# Sheet4.net
KiCad netlist of a schematic drawn in Altium Designer
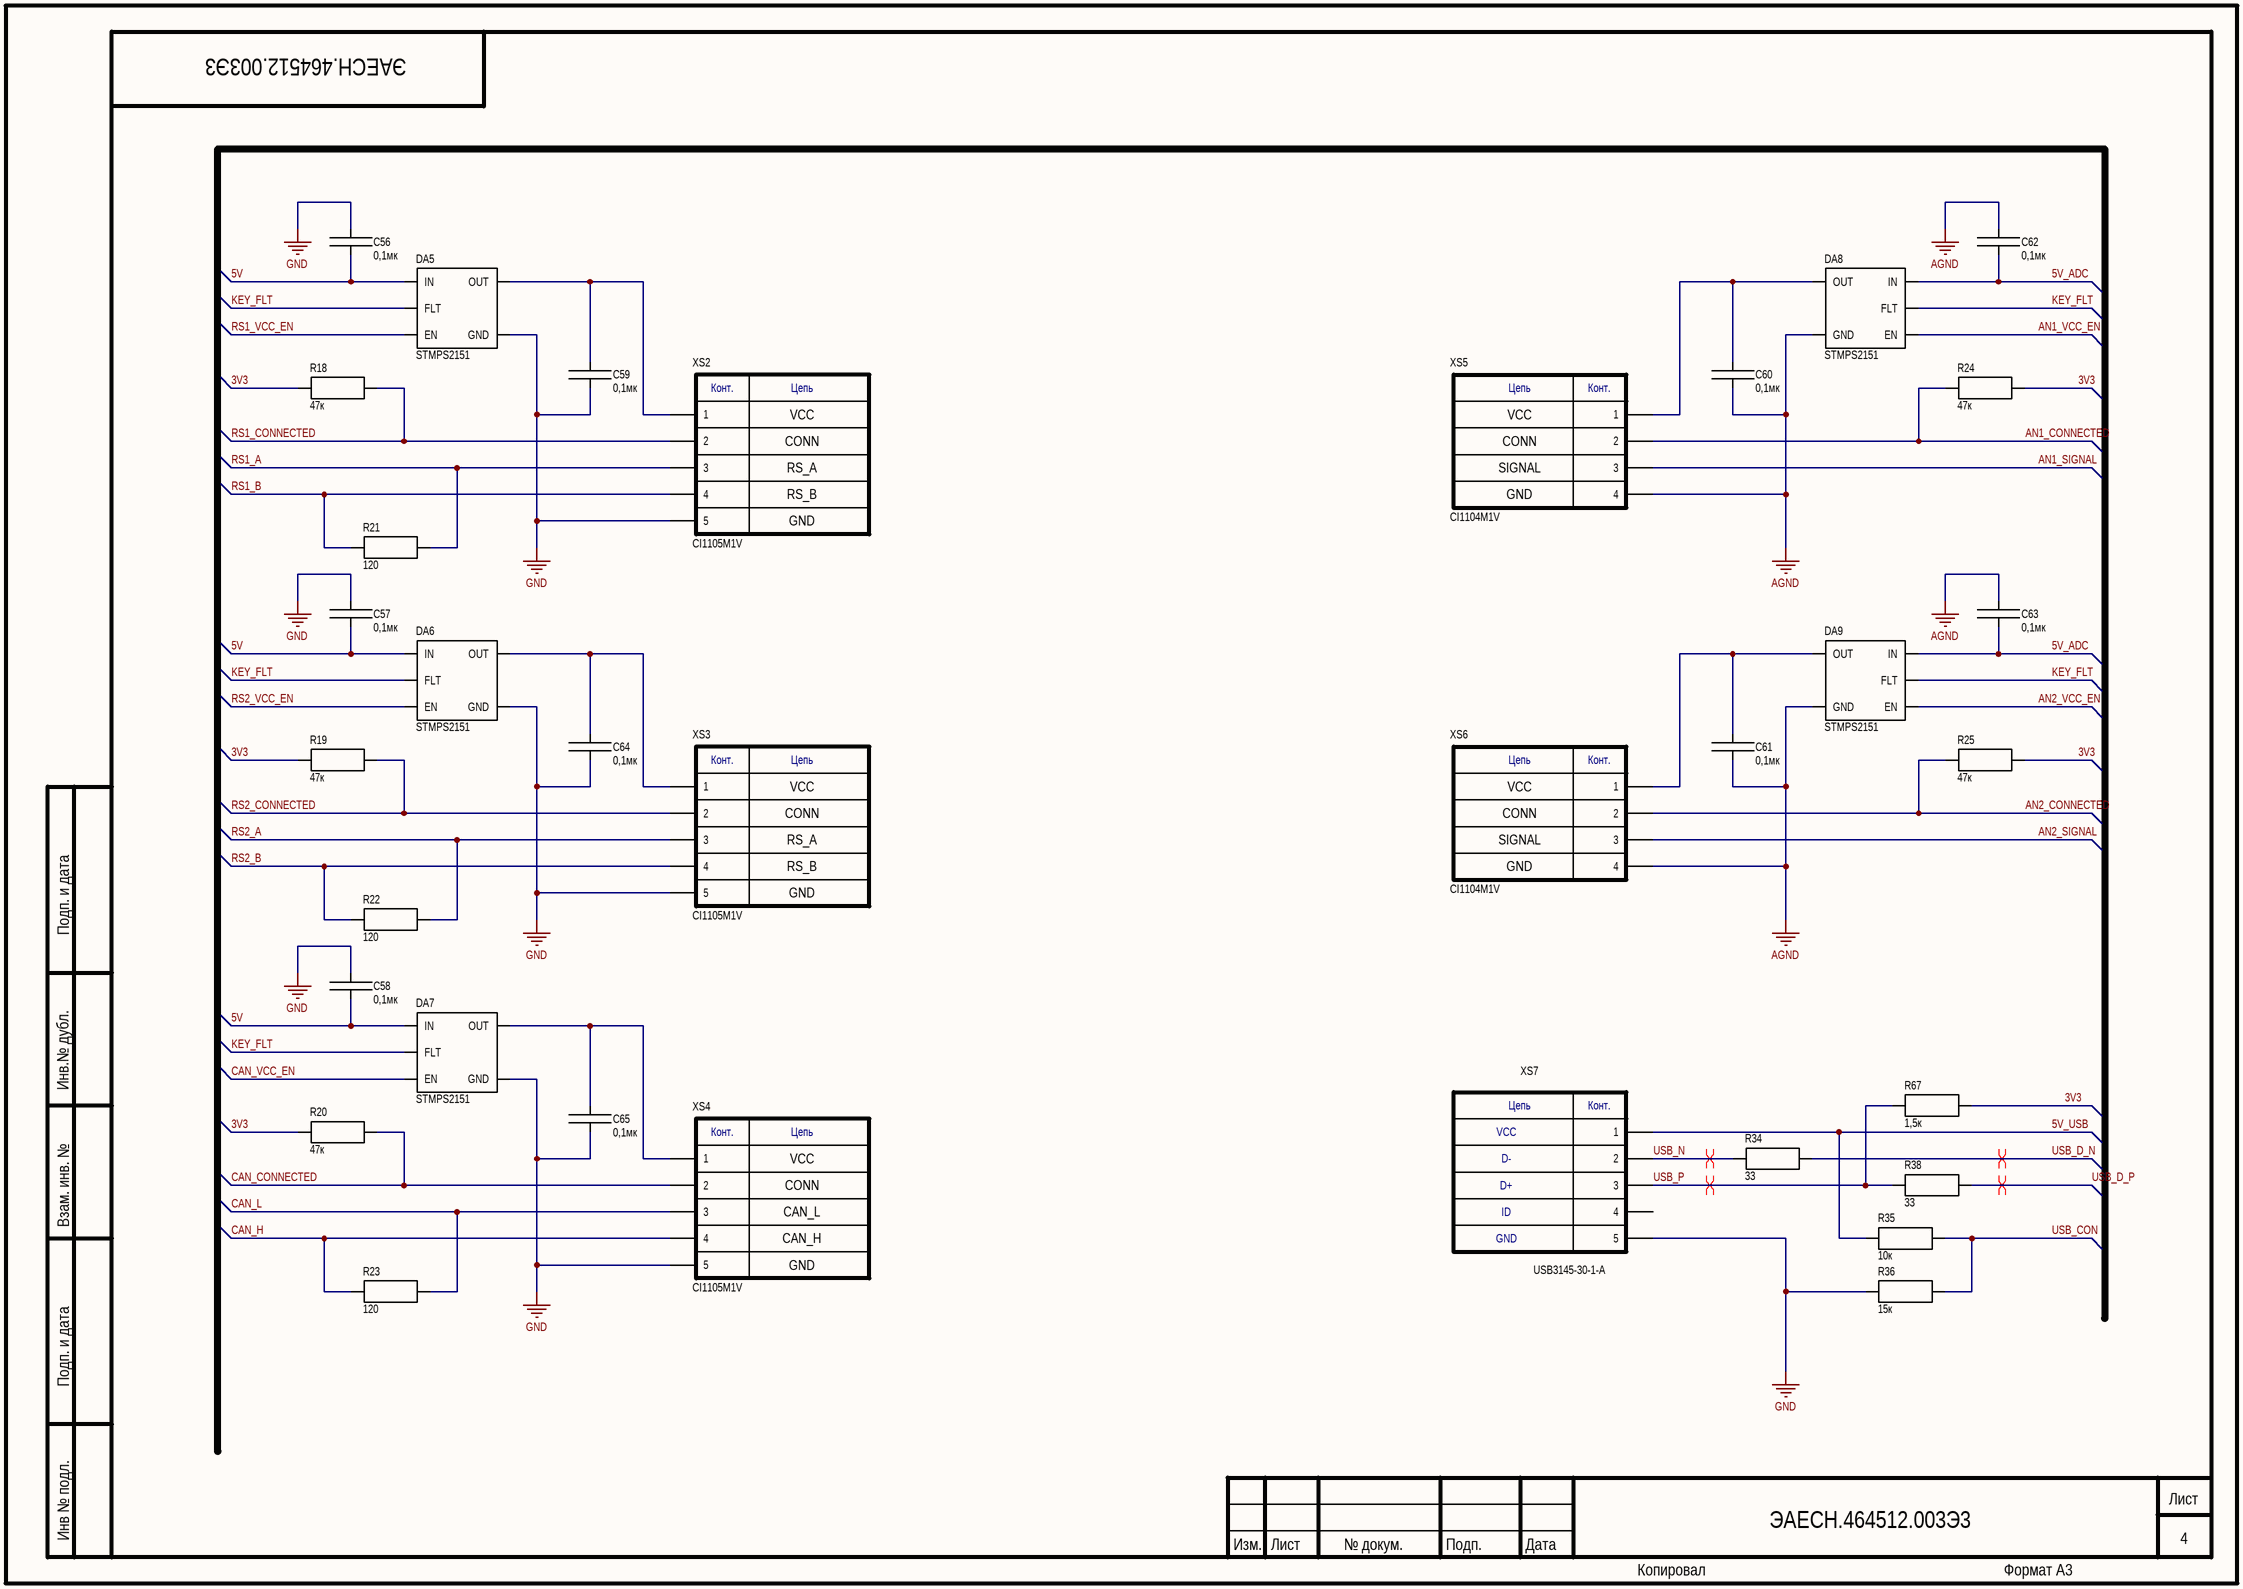
[diagram p0: Sheet4.SchDoc]

(export (version "E")
  (design (tool "Eeschema 10.0.6"))
  (components
    (comp (ref "C56")
      (value "0,1мк")
      (footprint "С0603")
      (fields (field (name "Comment") "C"))
      (libsource (lib "Schlib1") (part "C"))
    )
    (comp (ref "C57")
      (value "0,1мк")
      (footprint "С0603")
      (fields (field (name "Comment") "C"))
      (libsource (lib "Schlib1") (part "C"))
    )
    (comp (ref "C58")
      (value "0,1мк")
      (footprint "С0603")
      (fields (field (name "Comment") "C"))
      (libsource (lib "Schlib1") (part "C"))
    )
    (comp (ref "C59")
      (value "0,1мк")
      (footprint "С0603")
      (fields (field (name "Comment") "C"))
      (libsource (lib "Schlib1") (part "C"))
    )
    (comp (ref "C60")
      (value "0,1мк")
      (footprint "С0603")
      (fields (field (name "Comment") "C"))
      (libsource (lib "Schlib1") (part "C"))
    )
    (comp (ref "C61")
      (value "0,1мк")
      (footprint "С0603")
      (fields (field (name "Comment") "C"))
      (libsource (lib "Schlib1") (part "C"))
    )
    (comp (ref "C62")
      (value "0,1мк")
      (footprint "С0603")
      (fields (field (name "Comment") "C"))
      (libsource (lib "Schlib1") (part "C"))
    )
    (comp (ref "C63")
      (value "0,1мк")
      (footprint "С0603")
      (fields (field (name "Comment") "C"))
      (libsource (lib "Schlib1") (part "C"))
    )
    (comp (ref "C64")
      (value "0,1мк")
      (footprint "С0603")
      (fields (field (name "Comment") "C"))
      (libsource (lib "Schlib1") (part "C"))
    )
    (comp (ref "C65")
      (value "0,1мк")
      (footprint "С0603")
      (fields (field (name "Comment") "C"))
      (libsource (lib "Schlib1") (part "C"))
    )
    (comp (ref "DA5")
      (value "STMPS2151")
      (footprint "SOT-23-5")
      (libsource (lib "Schlib1") (part "STMPS21x1"))
    )
    (comp (ref "DA6")
      (value "STMPS2151")
      (footprint "SOT-23-5")
      (libsource (lib "Schlib1") (part "STMPS21x1"))
    )
    (comp (ref "DA7")
      (value "STMPS2151")
      (footprint "SOT-23-5")
      (libsource (lib "Schlib1") (part "STMPS21x1"))
    )
    (comp (ref "DA8")
      (value "STMPS2151")
      (footprint "SOT-23-5")
      (libsource (lib "Schlib1") (part "STMPS21x1"))
    )
    (comp (ref "DA9")
      (value "STMPS2151")
      (footprint "SOT-23-5")
      (libsource (lib "Schlib1") (part "STMPS21x1"))
    )
    (comp (ref "R18")
      (value "47к")
      (footprint "R0603")
      (fields (field (name "Comment") "R"))
      (libsource (lib "Schlib1") (part "R"))
    )
    (comp (ref "R19")
      (value "47к")
      (footprint "R0603")
      (fields (field (name "Comment") "R"))
      (libsource (lib "Schlib1") (part "R"))
    )
    (comp (ref "R20")
      (value "47к")
      (footprint "R0603")
      (fields (field (name "Comment") "R"))
      (libsource (lib "Schlib1") (part "R"))
    )
    (comp (ref "R21")
      (value "120")
      (footprint "R1206")
      (fields (field (name "Comment") "R"))
      (libsource (lib "Schlib1") (part "R"))
    )
    (comp (ref "R22")
      (value "120")
      (footprint "R1206")
      (fields (field (name "Comment") "R"))
      (libsource (lib "Schlib1") (part "R"))
    )
    (comp (ref "R23")
      (value "120")
      (footprint "R1206")
      (fields (field (name "Comment") "R"))
      (libsource (lib "Schlib1") (part "R"))
    )
    (comp (ref "R24")
      (value "47к")
      (footprint "R0603")
      (fields (field (name "Comment") "R"))
      (libsource (lib "Schlib1") (part "R"))
    )
    (comp (ref "R25")
      (value "47к")
      (footprint "R0603")
      (fields (field (name "Comment") "R"))
      (libsource (lib "Schlib1") (part "R"))
    )
    (comp (ref "R34")
      (value "33")
      (footprint "R0603")
      (fields (field (name "Comment") "R"))
      (libsource (lib "Schlib1") (part "R"))
    )
    (comp (ref "R35")
      (value "10к")
      (footprint "R0603")
      (fields (field (name "Comment") "R"))
      (libsource (lib "Schlib1") (part "R"))
    )
    (comp (ref "R36")
      (value "15к")
      (footprint "R0603")
      (fields (field (name "Comment") "R"))
      (libsource (lib "Schlib1") (part "R"))
    )
    (comp (ref "R38")
      (value "33")
      (footprint "R0603")
      (fields (field (name "Comment") "R"))
      (libsource (lib "Schlib1") (part "R"))
    )
    (comp (ref "R67")
      (value "1,5к")
      (footprint "R0603")
      (fields (field (name "Comment") "R"))
      (libsource (lib "Schlib1") (part "R"))
    )
    (comp (ref "XS2") (value "CI1105M1V") (footprint "СI1105М1V") (libsource (lib "Schlib1") (part "5pin")))
    (comp (ref "XS3") (value "CI1105M1V") (footprint "СI1105М1V") (libsource (lib "Schlib1") (part "5pin")))
    (comp (ref "XS4") (value "CI1105M1V") (footprint "СI1105М1V") (libsource (lib "Schlib1") (part "5pin")))
    (comp (ref "XS5") (value "СI1104М1V") (footprint "СI1104М1V") (libsource (lib "Schlib1") (part "4pin")))
    (comp (ref "XS6") (value "СI1104М1V") (footprint "СI1104М1V") (libsource (lib "Schlib1") (part "4pin")))
    (comp (ref "XS7")
      (value "USB3145-30-1-A")
      (footprint "USB3145-30-1")
      (libsource (lib "Schlib1") (part "USB"))
    )
  )
  (nets
    (net (code "1") (name "/3V3") (class "Default")
      (node (ref "R18") (pin "1") (pinfunction "1_1") (pintype "passive"))
      (node (ref "R19") (pin "1") (pinfunction "1_1") (pintype "passive"))
      (node (ref "R20") (pin "1") (pinfunction "1_1") (pintype "passive"))
      (node (ref "R24") (pin "1") (pinfunction "1_1") (pintype "passive"))
      (node (ref "R25") (pin "1") (pinfunction "1_1") (pintype "passive"))
      (node (ref "R67") (pin "2") (pinfunction "2_2") (pintype "passive"))
    )
    (net (code "2") (name "/5V") (class "Default")
      (node (ref "C56") (pin "2") (pinfunction "2_2") (pintype "passive"))
      (node (ref "C57") (pin "2") (pinfunction "2_2") (pintype "passive"))
      (node (ref "C58") (pin "2") (pinfunction "2_2") (pintype "passive"))
      (node (ref "DA5") (pin "5") (pinfunction "IN_5") (pintype "passive"))
      (node (ref "DA6") (pin "5") (pinfunction "IN_5") (pintype "passive"))
      (node (ref "DA7") (pin "5") (pinfunction "IN_5") (pintype "passive"))
    )
    (net (code "3") (name "/5V_ADC") (class "Default")
      (node (ref "C62") (pin "2") (pinfunction "2_2") (pintype "passive"))
      (node (ref "C63") (pin "2") (pinfunction "2_2") (pintype "passive"))
      (node (ref "DA8") (pin "5") (pinfunction "IN_5") (pintype "passive"))
      (node (ref "DA9") (pin "5") (pinfunction "IN_5") (pintype "passive"))
    )
    (net (code "4") (name "/5V_USB") (class "Default")
      (node (ref "R35") (pin "1") (pinfunction "1_1") (pintype "passive"))
      (node (ref "XS7") (pin "1") (pinfunction "1_1") (pintype "passive"))
    )
    (net (code "5") (name "/AN1_CONNECTED") (class "Default")
      (node (ref "R24") (pin "2") (pinfunction "2_2") (pintype "passive"))
      (node (ref "XS5") (pin "2") (pinfunction "2_2") (pintype "passive"))
    )
    (net (code "6") (name "/AN1_SIGNAL") (class "Default")
      (node (ref "XS5") (pin "3") (pinfunction "3_3") (pintype "passive"))
    )
    (net (code "7") (name "/AN1_VCC_EN") (class "Default")
      (node (ref "DA8") (pin "4") (pinfunction "EN_4") (pintype "passive"))
    )
    (net (code "8") (name "/AN2_CONNECTED") (class "Default")
      (node (ref "R25") (pin "2") (pinfunction "2_2") (pintype "passive"))
      (node (ref "XS6") (pin "2") (pinfunction "2_2") (pintype "passive"))
    )
    (net (code "9") (name "/AN2_SIGNAL") (class "Default")
      (node (ref "XS6") (pin "3") (pinfunction "3_3") (pintype "passive"))
    )
    (net (code "10") (name "/AN2_VCC_EN") (class "Default")
      (node (ref "DA9") (pin "4") (pinfunction "EN_4") (pintype "passive"))
    )
    (net (code "11") (name "/CAN_CONNECTED") (class "Default")
      (node (ref "R20") (pin "2") (pinfunction "2_2") (pintype "passive"))
      (node (ref "XS4") (pin "2") (pinfunction "2_2") (pintype "passive"))
    )
    (net (code "12") (name "/CAN_H") (class "Default")
      (node (ref "R23") (pin "1") (pinfunction "1_1") (pintype "passive"))
      (node (ref "XS4") (pin "4") (pinfunction "4_4") (pintype "passive"))
    )
    (net (code "13") (name "/CAN_L") (class "Default")
      (node (ref "R23") (pin "2") (pinfunction "2_2") (pintype "passive"))
      (node (ref "XS4") (pin "3") (pinfunction "3_3") (pintype "passive"))
    )
    (net (code "14") (name "/CAN_VCC_EN") (class "Default")
      (node (ref "DA7") (pin "4") (pinfunction "EN_4") (pintype "passive"))
    )
    (net (code "15") (name "/KEY_FLT") (class "Default")
      (node (ref "DA5") (pin "3") (pinfunction "FLT_3") (pintype "passive"))
      (node (ref "DA6") (pin "3") (pinfunction "FLT_3") (pintype "passive"))
      (node (ref "DA7") (pin "3") (pinfunction "FLT_3") (pintype "passive"))
      (node (ref "DA8") (pin "3") (pinfunction "FLT_3") (pintype "passive"))
      (node (ref "DA9") (pin "3") (pinfunction "FLT_3") (pintype "passive"))
    )
    (net (code "16") (name "/RS1_A") (class "Default")
      (node (ref "R21") (pin "2") (pinfunction "2_2") (pintype "passive"))
      (node (ref "XS2") (pin "3") (pinfunction "3_3") (pintype "passive"))
    )
    (net (code "17") (name "/RS1_B") (class "Default")
      (node (ref "R21") (pin "1") (pinfunction "1_1") (pintype "passive"))
      (node (ref "XS2") (pin "4") (pinfunction "4_4") (pintype "passive"))
    )
    (net (code "18") (name "/RS1_CONNECTED") (class "Default")
      (node (ref "R18") (pin "2") (pinfunction "2_2") (pintype "passive"))
      (node (ref "XS2") (pin "2") (pinfunction "2_2") (pintype "passive"))
    )
    (net (code "19") (name "/RS1_VCC_EN") (class "Default")
      (node (ref "DA5") (pin "4") (pinfunction "EN_4") (pintype "passive"))
    )
    (net (code "20") (name "/RS2_A") (class "Default")
      (node (ref "R22") (pin "2") (pinfunction "2_2") (pintype "passive"))
      (node (ref "XS3") (pin "3") (pinfunction "3_3") (pintype "passive"))
    )
    (net (code "21") (name "/RS2_B") (class "Default")
      (node (ref "R22") (pin "1") (pinfunction "1_1") (pintype "passive"))
      (node (ref "XS3") (pin "4") (pinfunction "4_4") (pintype "passive"))
    )
    (net (code "22") (name "/RS2_CONNECTED") (class "Default")
      (node (ref "R19") (pin "2") (pinfunction "2_2") (pintype "passive"))
      (node (ref "XS3") (pin "2") (pinfunction "2_2") (pintype "passive"))
    )
    (net (code "23") (name "/RS2_VCC_EN") (class "Default")
      (node (ref "DA6") (pin "4") (pinfunction "EN_4") (pintype "passive"))
    )
    (net (code "24") (name "/USB_CON") (class "Default")
      (node (ref "R35") (pin "2") (pinfunction "2_2") (pintype "passive"))
      (node (ref "R36") (pin "2") (pinfunction "2_2") (pintype "passive"))
    )
    (net (code "25") (name "/USB_D_N") (class "Default")
      (node (ref "R34") (pin "2") (pinfunction "2_2") (pintype "passive"))
    )
    (net (code "26") (name "/USB_D_P") (class "Default")
      (node (ref "R38") (pin "2") (pinfunction "2_2") (pintype "passive"))
    )
    (net (code "27") (name "/USB_N") (class "Default")
      (node (ref "R34") (pin "1") (pinfunction "1_1") (pintype "passive"))
      (node (ref "XS7") (pin "2") (pinfunction "2_2") (pintype "passive"))
    )
    (net (code "28") (name "/USB_P") (class "Default")
      (node (ref "R38") (pin "1") (pinfunction "1_1") (pintype "passive"))
      (node (ref "R67") (pin "1") (pinfunction "1_1") (pintype "passive"))
      (node (ref "XS7") (pin "3") (pinfunction "3_3") (pintype "passive"))
    )
    (net (code "29") (name "AGND") (class "Default")
      (node (ref "C60") (pin "2") (pinfunction "2_2") (pintype "passive"))
      (node (ref "C61") (pin "2") (pinfunction "2_2") (pintype "passive"))
      (node (ref "C62") (pin "1") (pinfunction "1_1") (pintype "passive"))
      (node (ref "C63") (pin "1") (pinfunction "1_1") (pintype "passive"))
      (node (ref "DA8") (pin "2") (pinfunction "GND_2") (pintype "passive"))
      (node (ref "DA9") (pin "2") (pinfunction "GND_2") (pintype "passive"))
      (node (ref "XS5") (pin "4") (pinfunction "4_4") (pintype "passive"))
      (node (ref "XS6") (pin "4") (pinfunction "4_4") (pintype "passive"))
    )
    (net (code "30") (name "GND") (class "Default")
      (node (ref "C56") (pin "1") (pinfunction "1_1") (pintype "passive"))
      (node (ref "C57") (pin "1") (pinfunction "1_1") (pintype "passive"))
      (node (ref "C58") (pin "1") (pinfunction "1_1") (pintype "passive"))
      (node (ref "C59") (pin "2") (pinfunction "2_2") (pintype "passive"))
      (node (ref "C64") (pin "2") (pinfunction "2_2") (pintype "passive"))
      (node (ref "C65") (pin "2") (pinfunction "2_2") (pintype "passive"))
      (node (ref "DA5") (pin "2") (pinfunction "GND_2") (pintype "passive"))
      (node (ref "DA6") (pin "2") (pinfunction "GND_2") (pintype "passive"))
      (node (ref "DA7") (pin "2") (pinfunction "GND_2") (pintype "passive"))
      (node (ref "R36") (pin "1") (pinfunction "1_1") (pintype "passive"))
      (node (ref "XS2") (pin "5") (pinfunction "5_5") (pintype "passive"))
      (node (ref "XS3") (pin "5") (pinfunction "5_5") (pintype "passive"))
      (node (ref "XS4") (pin "5") (pinfunction "5_5") (pintype "passive"))
      (node (ref "XS7") (pin "5") (pinfunction "5_5") (pintype "passive"))
    )
    (net (code "31") (name "Net-(DA5-OUT)") (class "Default")
      (node (ref "C59") (pin "1") (pinfunction "1_1") (pintype "passive"))
      (node (ref "DA5") (pin "1") (pinfunction "OUT_1") (pintype "passive"))
      (node (ref "XS2") (pin "1") (pinfunction "1_1") (pintype "passive"))
    )
    (net (code "32") (name "Net-(DA6-OUT)") (class "Default")
      (node (ref "C64") (pin "1") (pinfunction "1_1") (pintype "passive"))
      (node (ref "DA6") (pin "1") (pinfunction "OUT_1") (pintype "passive"))
      (node (ref "XS3") (pin "1") (pinfunction "1_1") (pintype "passive"))
    )
    (net (code "33") (name "Net-(DA7-OUT)") (class "Default")
      (node (ref "C65") (pin "1") (pinfunction "1_1") (pintype "passive"))
      (node (ref "DA7") (pin "1") (pinfunction "OUT_1") (pintype "passive"))
      (node (ref "XS4") (pin "1") (pinfunction "1_1") (pintype "passive"))
    )
    (net (code "34") (name "Net-(DA8-OUT)") (class "Default")
      (node (ref "C60") (pin "1") (pinfunction "1_1") (pintype "passive"))
      (node (ref "DA8") (pin "1") (pinfunction "OUT_1") (pintype "passive"))
      (node (ref "XS5") (pin "1") (pinfunction "1_1") (pintype "passive"))
    )
    (net (code "35") (name "Net-(DA9-OUT)") (class "Default")
      (node (ref "C61") (pin "1") (pinfunction "1_1") (pintype "passive"))
      (node (ref "DA9") (pin "1") (pinfunction "OUT_1") (pintype "passive"))
      (node (ref "XS6") (pin "1") (pinfunction "1_1") (pintype "passive"))
    )
    (net (code "36") (name "unconnected-(XS7-Pad4)") (class "Default")
      (node (ref "XS7") (pin "4") (pinfunction "4_4") (pintype "passive"))
    )
  )
)
